# JP_WING_R.net
KiCad netlist of a schematic drawn in EasyEDA Pro
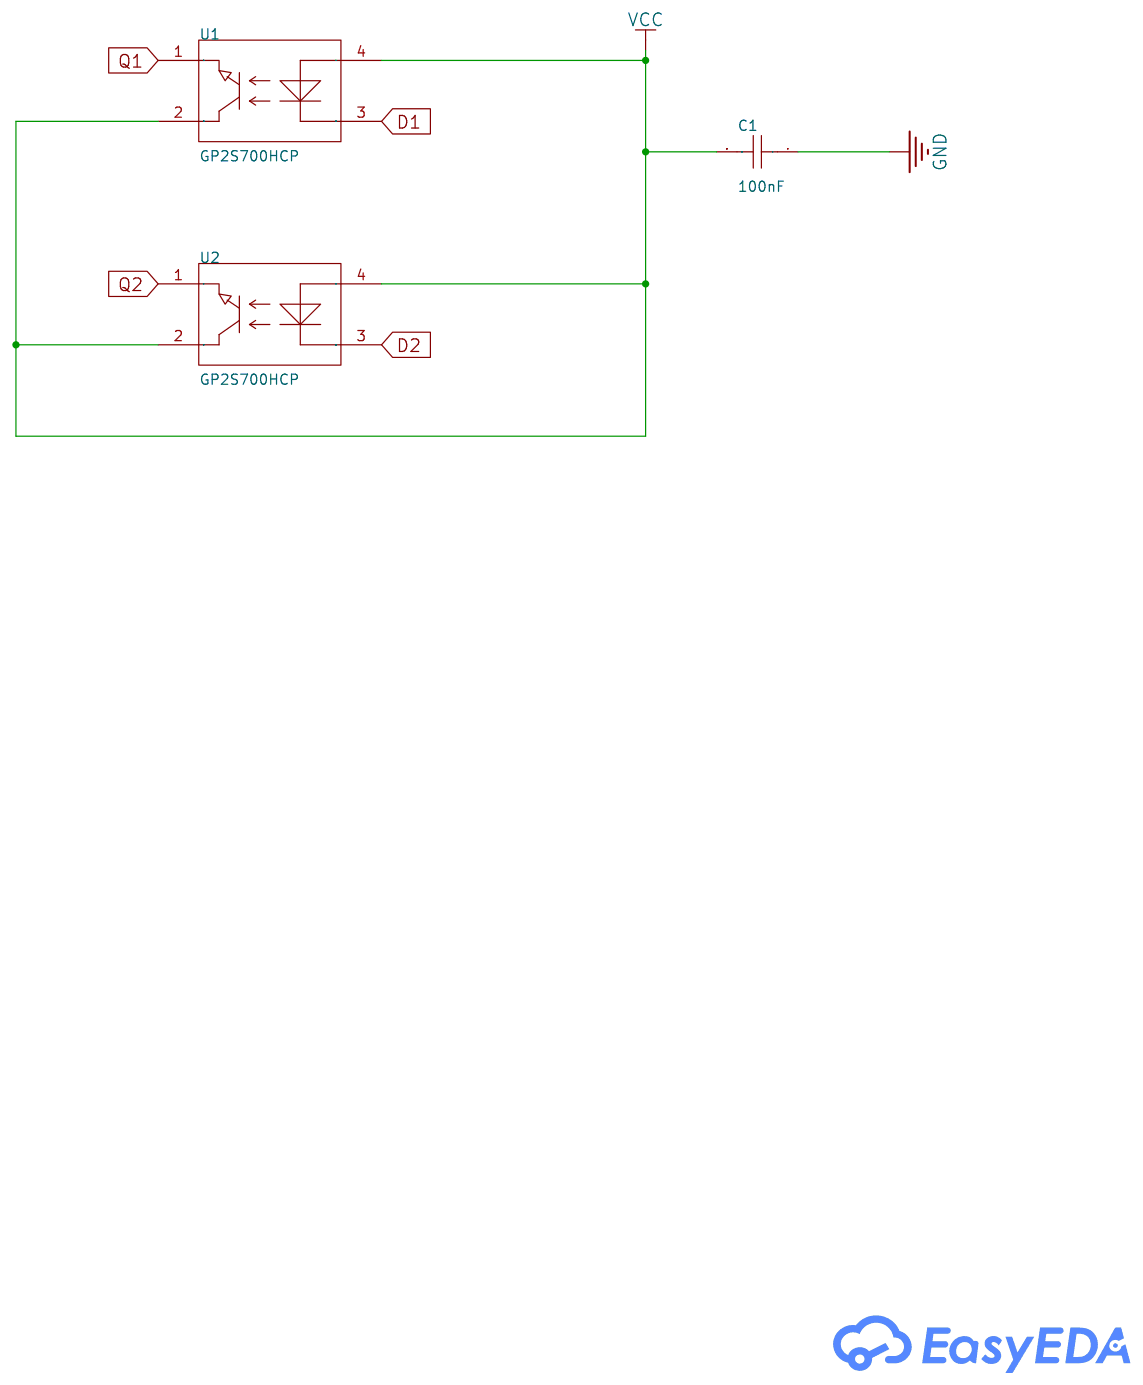
[diagram p0: schematic sheet]

(export (version "E")
  (design (tool "Eeschema 10.0.6"))
  (components
    (comp (ref "C1")
      (value "100nF")
      (footprint "easyedapro:C0603")
      (libsource (lib "easyedapro") (part "CAP"))
    )
    (comp (ref "U1")
      (value "GP2S700HCP")
      (footprint "easyedapro:OPTO-SMD_GP2S700HCP")
      (description "Sensing Distance:5.5mm Collector Current (Max):20mA")
      (fields (field (name "Manufacturer") "SHARP(夏普)"))
      (libsource (lib "easyedapro") (part "GP2S700HCP"))
    )
    (comp (ref "U2")
      (value "GP2S700HCP")
      (footprint "easyedapro:OPTO-SMD_GP2S700HCP")
      (description "Sensing Distance:5.5mm Collector Current (Max):20mA")
      (fields (field (name "Manufacturer") "SHARP(夏普)"))
      (libsource (lib "easyedapro") (part "GP2S700HCP"))
    )
  )
  (nets
    (net (code "1") (name "D1") (class "Default")
      (node (ref "U1") (pin "3") (pinfunction "3_3") (pintype "input"))
    )
    (net (code "2") (name "D2") (class "Default")
      (node (ref "U2") (pin "3") (pinfunction "3_3") (pintype "input"))
    )
    (net (code "3") (name "GND") (class "Default")
      (node (ref "C1") (pin "1") (pinfunction "1_1") (pintype "input"))
    )
    (net (code "4") (name "Q1") (class "Default")
      (node (ref "U1") (pin "1") (pinfunction "1_1") (pintype "input"))
    )
    (net (code "5") (name "Q2") (class "Default")
      (node (ref "U2") (pin "1") (pinfunction "1_1") (pintype "input"))
    )
    (net (code "6") (name "VCC") (class "Default")
      (node (ref "C1") (pin "2") (pinfunction "2_2") (pintype "input"))
      (node (ref "U1") (pin "2") (pinfunction "2_2") (pintype "input"))
      (node (ref "U1") (pin "4") (pinfunction "4_4") (pintype "input"))
      (node (ref "U2") (pin "2") (pinfunction "2_2") (pintype "input"))
      (node (ref "U2") (pin "4") (pinfunction "4_4") (pintype "input"))
    )
  )
)
